# SCH_ESP-CellCore_USB_Interlock_RevA3_1.net
KiCad netlist of a schematic drawn in EasyEDA
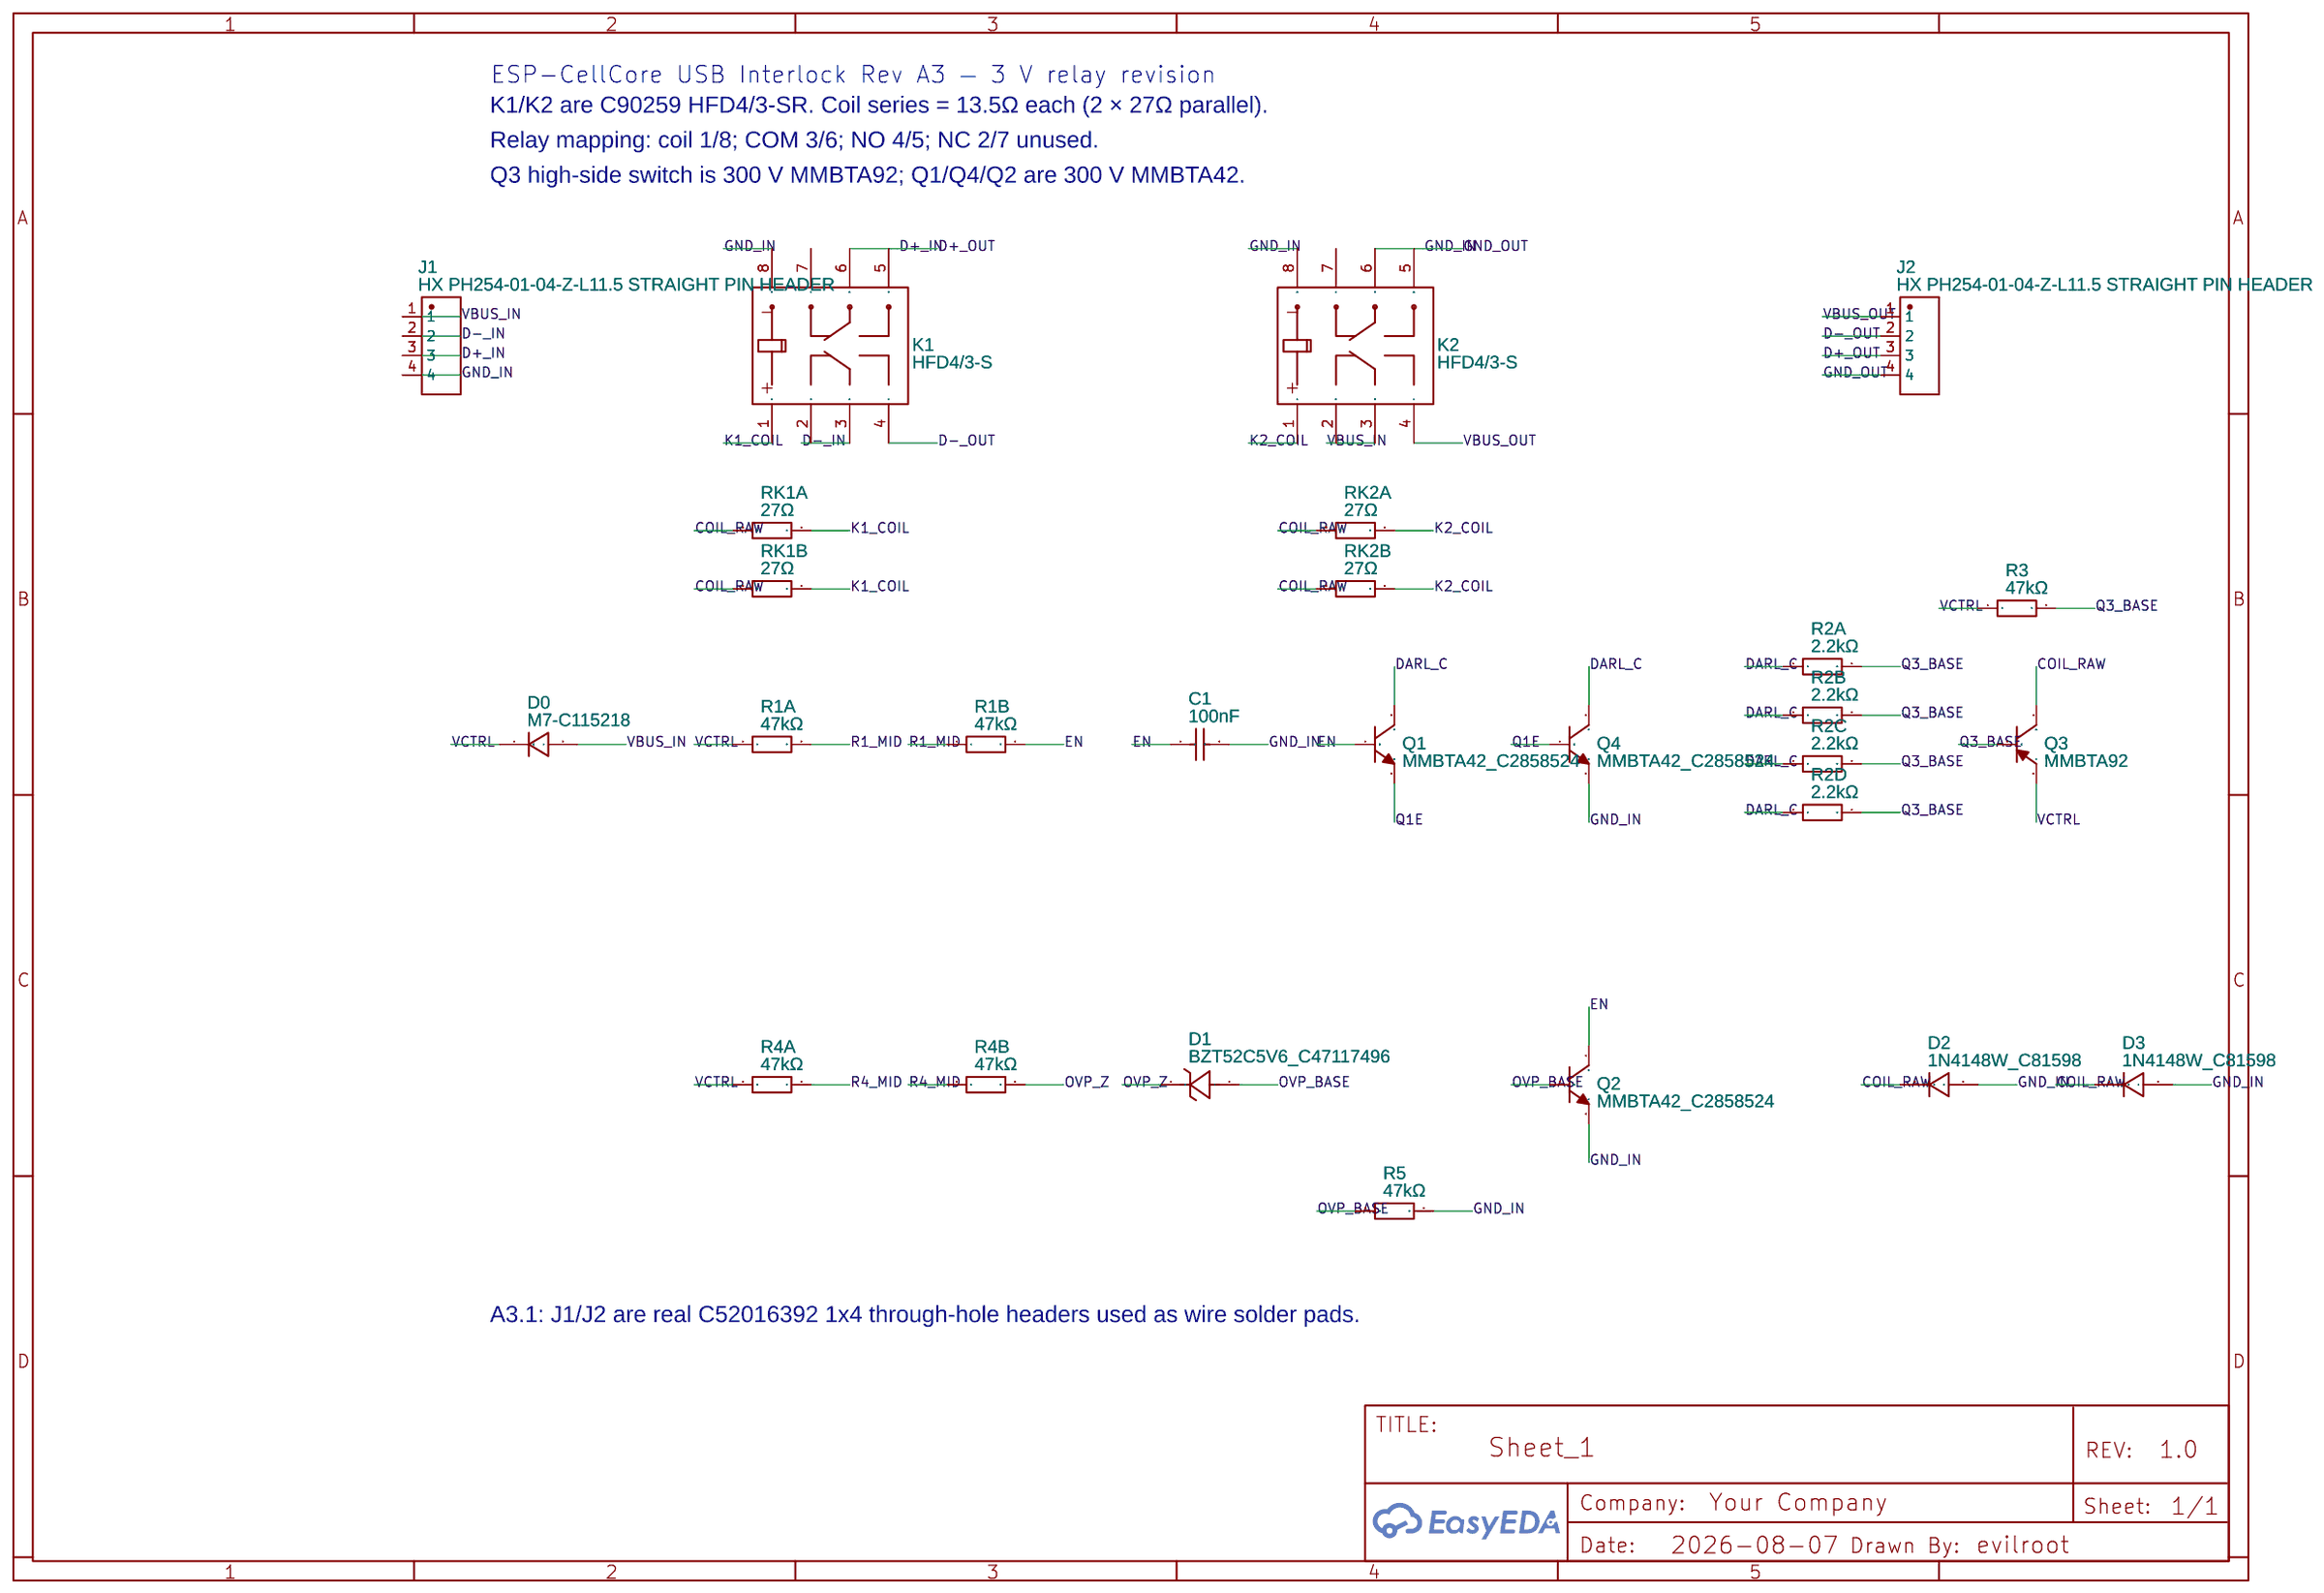
[diagram p0: schematic sheet]

(export (version "E")
  (design (tool "Eeschema 10.0.6"))
  (components
    (comp (ref "C1")
      (value "100nF")
      (fields
        (field (name "Manufacturer Part") "C0805C104K5RAC7800")
        (field (name "Manufacturer") "KEMET(基美)")
      )
      (libsource (lib "") (part "C0805C104K5RACTU"))
    )
    (comp (ref "D0")
      (value "M7-C115218")
      (fields (field (name "Manufacturer Part") "M7") (field (name "Manufacturer") "晶导微电子"))
      (libsource (lib "") (part "M7-C115218"))
    )
    (comp (ref "D1")
      (value "BZT52C5V6_C47117496")
      (fields (field (name "Manufacturer Part") "BZT52C5V6") (field (name "Manufacturer") "baocheng(宝乘)"))
      (libsource (lib "") (part "BZT52C5V6_C47117496"))
    )
    (comp (ref "D2")
      (value "1N4148W_C81598")
      (fields (field (name "Manufacturer Part") "1N4148W") (field (name "Manufacturer") "ST(先科)"))
      (libsource (lib "") (part "1N4148W_C81598"))
    )
    (comp (ref "D3")
      (value "1N4148W_C81598")
      (fields (field (name "Manufacturer Part") "1N4148W") (field (name "Manufacturer") "ST(先科)"))
      (libsource (lib "") (part "1N4148W_C81598"))
    )
    (comp (ref "J1")
      (value "HX PH254-01-04-Z-L11.5 STRAIGHT PIN HEADER")
      (fields
        (field (name "Manufacturer Part") "HX PH254-01-04-Z-L11.5 straight pin header")
        (field (name "Manufacturer") "hanxia(韩下)")
      )
      (libsource (lib "") (part "HX PH254-01-04-Z-L11.5 STRAIGHT PIN HEADER"))
    )
    (comp (ref "J2")
      (value "HX PH254-01-04-Z-L11.5 STRAIGHT PIN HEADER")
      (fields
        (field (name "Manufacturer Part") "HX PH254-01-04-Z-L11.5 straight pin header")
        (field (name "Manufacturer") "hanxia(韩下)")
      )
      (libsource (lib "") (part "HX PH254-01-04-Z-L11.5 STRAIGHT PIN HEADER"))
    )
    (comp (ref "K1")
      (value "HFD4/3-S")
      (fields (field (name "Manufacturer Part") "HFD4/3-SR") (field (name "Manufacturer") "HF(宏发)"))
      (libsource (lib "") (part "HFD4/3-S"))
    )
    (comp (ref "K2")
      (value "HFD4/3-S")
      (fields (field (name "Manufacturer Part") "HFD4/3-SR") (field (name "Manufacturer") "HF(宏发)"))
      (libsource (lib "") (part "HFD4/3-S"))
    )
    (comp (ref "Q1")
      (value "MMBTA42_C2858524")
      (fields (field (name "Manufacturer Part") "MMBTA42") (field (name "Manufacturer") "MDD(辰达半导体)"))
      (libsource (lib "") (part "MMBTA42_C2858524"))
    )
    (comp (ref "Q2")
      (value "MMBTA42_C2858524")
      (fields (field (name "Manufacturer Part") "MMBTA42") (field (name "Manufacturer") "MDD(辰达半导体)"))
      (libsource (lib "") (part "MMBTA42_C2858524"))
    )
    (comp (ref "Q3")
      (value "MMBTA92")
      (fields (field (name "Manufacturer") "GOODWORK(固得沃克)"))
      (libsource (lib "") (part "MMBTA92"))
    )
    (comp (ref "Q4")
      (value "MMBTA42_C2858524")
      (fields (field (name "Manufacturer Part") "MMBTA42") (field (name "Manufacturer") "MDD(辰达半导体)"))
      (libsource (lib "") (part "MMBTA42_C2858524"))
    )
    (comp (ref "R1A")
      (value "47kΩ")
      (fields (field (name "Manufacturer Part") "AC0805FR-0747KL") (field (name "Manufacturer") "YAGEO(国巨)"))
      (libsource (lib "") (part "AC0805FR-0747KL_4"))
    )
    (comp (ref "R1B")
      (value "47kΩ")
      (fields (field (name "Manufacturer Part") "AC0805FR-0747KL") (field (name "Manufacturer") "YAGEO(国巨)"))
      (libsource (lib "") (part "AC0805FR-0747KL_2"))
    )
    (comp (ref "R2A")
      (value "2.2kΩ")
      (fields
        (field (name "Manufacturer Part") "0805W8F2201T5E")
        (field (name "Manufacturer") "UNI-ROYAL(厚声)")
      )
      (libsource (lib "") (part "0805W8F2201T5E_3"))
    )
    (comp (ref "R2B")
      (value "2.2kΩ")
      (fields
        (field (name "Manufacturer Part") "0805W8F2201T5E")
        (field (name "Manufacturer") "UNI-ROYAL(厚声)")
      )
      (libsource (lib "") (part "0805W8F2201T5E_2"))
    )
    (comp (ref "R2C")
      (value "2.2kΩ")
      (fields
        (field (name "Manufacturer Part") "0805W8F2201T5E")
        (field (name "Manufacturer") "UNI-ROYAL(厚声)")
      )
      (libsource (lib "") (part "0805W8F2201T5E"))
    )
    (comp (ref "R2D")
      (value "2.2kΩ")
      (fields
        (field (name "Manufacturer Part") "0805W8F2201T5E")
        (field (name "Manufacturer") "UNI-ROYAL(厚声)")
      )
      (libsource (lib "") (part "0805W8F2201T5E_1"))
    )
    (comp (ref "R3")
      (value "47kΩ")
      (fields (field (name "Manufacturer Part") "AC0805FR-0747KL") (field (name "Manufacturer") "YAGEO(国巨)"))
      (libsource (lib "") (part "AC0805FR-0747KL"))
    )
    (comp (ref "R4A")
      (value "47kΩ")
      (fields (field (name "Manufacturer Part") "AC0805FR-0747KL") (field (name "Manufacturer") "YAGEO(国巨)"))
      (libsource (lib "") (part "AC0805FR-0747KL_1"))
    )
    (comp (ref "R4B")
      (value "47kΩ")
      (fields (field (name "Manufacturer Part") "AC0805FR-0747KL") (field (name "Manufacturer") "YAGEO(国巨)"))
      (libsource (lib "") (part "AC0805FR-0747KL_3"))
    )
    (comp (ref "R5")
      (value "47kΩ")
      (fields (field (name "Manufacturer Part") "AC0805FR-0747KL") (field (name "Manufacturer") "YAGEO(国巨)"))
      (libsource (lib "") (part "AC0805FR-0747KL"))
    )
    (comp (ref "RK1A")
      (value "27Ω")
      (fields (field (name "Manufacturer Part") "CR0805F827R0G") (field (name "Manufacturer") "LIZ(丽智电子)"))
      (libsource (lib "") (part "CR0805F827R0G_2"))
    )
    (comp (ref "RK1B")
      (value "27Ω")
      (fields (field (name "Manufacturer Part") "CR0805F827R0G") (field (name "Manufacturer") "LIZ(丽智电子)"))
      (libsource (lib "") (part "CR0805F827R0G"))
    )
    (comp (ref "RK2A")
      (value "27Ω")
      (fields (field (name "Manufacturer Part") "CR0805F827R0G") (field (name "Manufacturer") "LIZ(丽智电子)"))
      (libsource (lib "") (part "CR0805F827R0G_1"))
    )
    (comp (ref "RK2B")
      (value "27Ω")
      (fields (field (name "Manufacturer Part") "CR0805F827R0G") (field (name "Manufacturer") "LIZ(丽智电子)"))
      (libsource (lib "") (part "CR0805F827R0G_3"))
    )
  )
  (nets
    (net (code "1") (name "/COIL_RAW") (class "Default")
      (node (ref "D2") (pin "1") (pinfunction "K_1") (pintype "unspecified"))
      (node (ref "D3") (pin "1") (pinfunction "K_1") (pintype "unspecified"))
      (node (ref "Q3") (pin "3") (pinfunction "C_3") (pintype "input"))
      (node (ref "RK1A") (pin "1") (pinfunction "1_1") (pintype "input"))
      (node (ref "RK1B") (pin "1") (pinfunction "1_1") (pintype "input"))
      (node (ref "RK2A") (pin "1") (pinfunction "1_1") (pintype "input"))
      (node (ref "RK2B") (pin "1") (pinfunction "1_1") (pintype "input"))
    )
    (net (code "2") (name "/D+_IN") (class "Default")
      (node (ref "J1") (pin "3") (pinfunction "3_3") (pintype "unspecified"))
      (node (ref "J2") (pin "3") (pinfunction "3_3") (pintype "unspecified"))
      (node (ref "K1") (pin "5") (pinfunction "5_5") (pintype "input"))
      (node (ref "K1") (pin "6") (pinfunction "6_6") (pintype "input"))
    )
    (net (code "3") (name "/D-_IN") (class "Default")
      (node (ref "J1") (pin "2") (pinfunction "2_2") (pintype "unspecified"))
      (node (ref "K1") (pin "3") (pinfunction "3_3") (pintype "input"))
    )
    (net (code "4") (name "/D-_OUT") (class "Default")
      (node (ref "J2") (pin "2") (pinfunction "2_2") (pintype "unspecified"))
      (node (ref "K1") (pin "4") (pinfunction "4_4") (pintype "input"))
    )
    (net (code "5") (name "/DARL_C") (class "Default")
      (node (ref "Q1") (pin "3") (pinfunction "C_3") (pintype "input"))
      (node (ref "Q4") (pin "3") (pinfunction "C_3") (pintype "input"))
      (node (ref "R2A") (pin "1") (pinfunction "1_1") (pintype "input"))
      (node (ref "R2B") (pin "1") (pinfunction "1_1") (pintype "input"))
      (node (ref "R2C") (pin "1") (pinfunction "1_1") (pintype "input"))
      (node (ref "R2D") (pin "1") (pinfunction "1_1") (pintype "input"))
    )
    (net (code "6") (name "/EN") (class "Default")
      (node (ref "C1") (pin "1") (pinfunction "1_1") (pintype "input"))
      (node (ref "Q1") (pin "1") (pinfunction "B_1") (pintype "input"))
      (node (ref "Q2") (pin "3") (pinfunction "C_3") (pintype "input"))
      (node (ref "R1B") (pin "2") (pinfunction "2_2") (pintype "unspecified"))
    )
    (net (code "7") (name "/GND_IN") (class "Default")
      (node (ref "C1") (pin "2") (pinfunction "2_2") (pintype "input"))
      (node (ref "D2") (pin "2") (pinfunction "A_2") (pintype "unspecified"))
      (node (ref "D3") (pin "2") (pinfunction "A_2") (pintype "unspecified"))
      (node (ref "J1") (pin "4") (pinfunction "4_4") (pintype "unspecified"))
      (node (ref "J2") (pin "4") (pinfunction "4_4") (pintype "unspecified"))
      (node (ref "K1") (pin "8") (pinfunction "8_8") (pintype "input"))
      (node (ref "K2") (pin "5") (pinfunction "5_5") (pintype "input"))
      (node (ref "K2") (pin "6") (pinfunction "6_6") (pintype "input"))
      (node (ref "K2") (pin "8") (pinfunction "8_8") (pintype "input"))
      (node (ref "Q2") (pin "2") (pinfunction "E_2") (pintype "input"))
      (node (ref "Q4") (pin "2") (pinfunction "E_2") (pintype "input"))
      (node (ref "R5") (pin "2") (pinfunction "2_2") (pintype "unspecified"))
    )
    (net (code "8") (name "/K1_COIL") (class "Default")
      (node (ref "K1") (pin "1") (pinfunction "1_1") (pintype "input"))
      (node (ref "RK1A") (pin "2") (pinfunction "2_2") (pintype "input"))
      (node (ref "RK1B") (pin "2") (pinfunction "2_2") (pintype "input"))
    )
    (net (code "9") (name "/K2_COIL") (class "Default")
      (node (ref "K2") (pin "1") (pinfunction "1_1") (pintype "input"))
      (node (ref "RK2A") (pin "2") (pinfunction "2_2") (pintype "input"))
      (node (ref "RK2B") (pin "2") (pinfunction "2_2") (pintype "input"))
    )
    (net (code "10") (name "/OVP_BASE") (class "Default")
      (node (ref "D1") (pin "2") (pinfunction "A_2") (pintype "unspecified"))
      (node (ref "Q2") (pin "1") (pinfunction "B_1") (pintype "input"))
      (node (ref "R5") (pin "1") (pinfunction "1_1") (pintype "unspecified"))
    )
    (net (code "11") (name "/OVP_Z") (class "Default")
      (node (ref "D1") (pin "1") (pinfunction "C_1") (pintype "unspecified"))
      (node (ref "R4B") (pin "2") (pinfunction "2_2") (pintype "unspecified"))
    )
    (net (code "12") (name "/Q1E") (class "Default")
      (node (ref "Q1") (pin "2") (pinfunction "E_2") (pintype "input"))
      (node (ref "Q4") (pin "1") (pinfunction "B_1") (pintype "input"))
    )
    (net (code "13") (name "/Q3_BASE") (class "Default")
      (node (ref "Q3") (pin "1") (pinfunction "B_1") (pintype "input"))
      (node (ref "R2A") (pin "2") (pinfunction "2_2") (pintype "input"))
      (node (ref "R2B") (pin "2") (pinfunction "2_2") (pintype "input"))
      (node (ref "R2C") (pin "2") (pinfunction "2_2") (pintype "input"))
      (node (ref "R2D") (pin "2") (pinfunction "2_2") (pintype "input"))
      (node (ref "R3") (pin "2") (pinfunction "2_2") (pintype "unspecified"))
    )
    (net (code "14") (name "/R1_MID") (class "Default")
      (node (ref "R1A") (pin "2") (pinfunction "2_2") (pintype "unspecified"))
      (node (ref "R1B") (pin "1") (pinfunction "1_1") (pintype "unspecified"))
    )
    (net (code "15") (name "/R4_MID") (class "Default")
      (node (ref "R4A") (pin "2") (pinfunction "2_2") (pintype "unspecified"))
      (node (ref "R4B") (pin "1") (pinfunction "1_1") (pintype "unspecified"))
    )
    (net (code "16") (name "/VBUS_IN") (class "Default")
      (node (ref "D0") (pin "2") (pinfunction "A_2") (pintype "unspecified"))
      (node (ref "J1") (pin "1") (pinfunction "1_1") (pintype "unspecified"))
      (node (ref "K2") (pin "3") (pinfunction "3_3") (pintype "input"))
    )
    (net (code "17") (name "/VBUS_OUT") (class "Default")
      (node (ref "J2") (pin "1") (pinfunction "1_1") (pintype "unspecified"))
      (node (ref "K2") (pin "4") (pinfunction "4_4") (pintype "input"))
    )
    (net (code "18") (name "/VCTRL") (class "Default")
      (node (ref "D0") (pin "1") (pinfunction "C_1") (pintype "unspecified"))
      (node (ref "Q3") (pin "2") (pinfunction "E_2") (pintype "input"))
      (node (ref "R1A") (pin "1") (pinfunction "1_1") (pintype "unspecified"))
      (node (ref "R3") (pin "1") (pinfunction "1_1") (pintype "unspecified"))
      (node (ref "R4A") (pin "1") (pinfunction "1_1") (pintype "unspecified"))
    )
    (net (code "19") (name "unconnected-(K1-Pad2)") (class "Default")
      (node (ref "K1") (pin "2") (pinfunction "2_2") (pintype "input"))
    )
    (net (code "20") (name "unconnected-(K1-Pad7)") (class "Default")
      (node (ref "K1") (pin "7") (pinfunction "7_7") (pintype "input"))
    )
    (net (code "21") (name "unconnected-(K2-Pad2)") (class "Default")
      (node (ref "K2") (pin "2") (pinfunction "2_2") (pintype "input"))
    )
    (net (code "22") (name "unconnected-(K2-Pad7)") (class "Default")
      (node (ref "K2") (pin "7") (pinfunction "7_7") (pintype "input"))
    )
  )
)
